# COTS.net
KiCad netlist of a schematic drawn in EAGLE
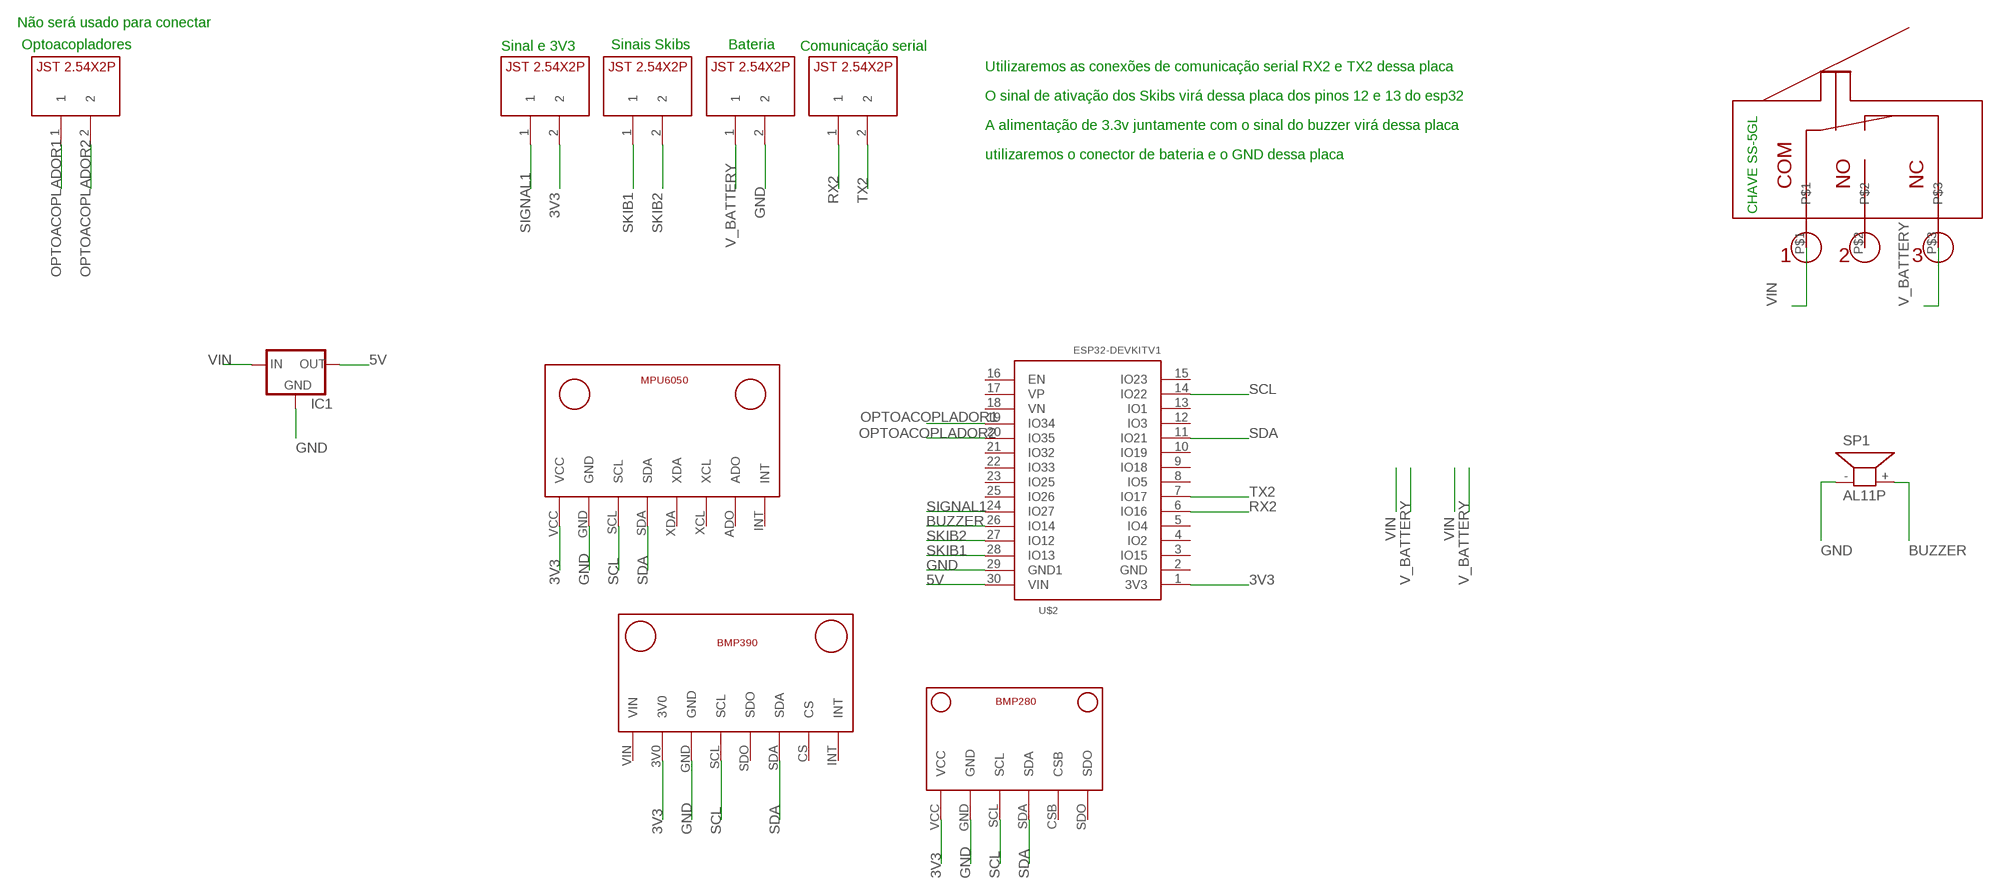
[diagram p0: schematic, sheet 1]

(export (version "E")
  (design (tool "Eeschema 10.0.6"))
  (components
    (comp (ref "IC1")
      (value "78XXL")
      (footprint "eagle-import:78XXL")
      (libsource (lib "eagle-import") (part "78XXL"))
    )
    (comp (ref "SP1")
      (value "AL11P")
      (footprint "eagle-import:AL11P")
      (libsource (lib "eagle-import") (part "AL11P"))
    )
    (comp (ref "U$1")
      (value "MPU6050V1")
      (footprint "eagle-import:MPU6050_FOOTPRINT")
      (libsource (lib "eagle-import") (part "MPU6050V1"))
    )
    (comp (ref "U$2")
      (value "ESP32DEVKITV1")
      (footprint "eagle-import:ESP32-DEVKITV1")
      (libsource (lib "eagle-import") (part "ESP32DEVKITV1"))
    )
    (comp (ref "U$3")
      (value "BMP390V1")
      (footprint "eagle-import:BMP390_FOOTPRINT")
      (libsource (lib "eagle-import") (part "BMP390V1"))
    )
    (comp (ref "U$4")
      (value "JST2.54X2P")
      (footprint "eagle-import:JST2.54X2P_FOOTPRINT")
      (libsource (lib "eagle-import") (part "JST2.54X2P"))
    )
    (comp (ref "U$5")
      (value "JST2.54X2P")
      (footprint "eagle-import:JST2.54X2P_FOOTPRINT")
      (libsource (lib "eagle-import") (part "JST2.54X2P"))
    )
    (comp (ref "U$6")
      (value "JST2.54X2P")
      (footprint "eagle-import:JST2.54X2P_FOOTPRINT")
      (libsource (lib "eagle-import") (part "JST2.54X2P"))
    )
    (comp (ref "U$7")
      (value "JST2.54X2P")
      (footprint "eagle-import:JST2.54X2P_FOOTPRINT")
      (libsource (lib "eagle-import") (part "JST2.54X2P"))
    )
    (comp (ref "U$8")
      (value "CHAVE_SS-5GL")
      (footprint "eagle-import:CHAVESS-5GL")
      (libsource (lib "eagle-import") (part "CHAVE_SS-5GL"))
    )
    (comp (ref "U$9")
      (value "JST2.54X2P")
      (footprint "eagle-import:JST2.54X2P_FOOTPRINT")
      (libsource (lib "eagle-import") (part "JST2.54X2P"))
    )
    (comp (ref "U$10")
      (value "BMP280V1")
      (footprint "eagle-import:BMP280_FOOTPRINT")
      (libsource (lib "eagle-import") (part "BMP280V1"))
    )
  )
  (nets
    (net (code "1") (name "/3V3") (class "Default")
      (node (ref "U$1") (pin "VCC") (pinfunction "VCC_VCC") (pintype "bidirectional"))
      (node (ref "U$10") (pin "VCC") (pinfunction "VCC_VCC") (pintype "bidirectional"))
      (node (ref "U$2") (pin "1") (pinfunction "3V3_1") (pintype "bidirectional"))
      (node (ref "U$3") (pin "3V0") (pinfunction "3V0_3V0") (pintype "bidirectional"))
      (node (ref "U$5") (pin "2") (pinfunction "2_2") (pintype "bidirectional"))
    )
    (net (code "2") (name "/5V") (class "Default")
      (node (ref "IC1") (pin "OUT") (pinfunction "OUT_OUT") (pintype "passive"))
      (node (ref "U$2") (pin "30") (pinfunction "VIN_30") (pintype "bidirectional"))
    )
    (net (code "3") (name "/BUZZER") (class "Default")
      (node (ref "SP1") (pin "+") (pinfunction "2_+") (pintype "passive"))
      (node (ref "U$2") (pin "26") (pinfunction "IO14_26") (pintype "bidirectional"))
    )
    (net (code "4") (name "/GND") (class "Default")
      (node (ref "IC1") (pin "GND") (pinfunction "GND_GND") (pintype "input"))
      (node (ref "SP1") (pin "-") (pinfunction "1_-") (pintype "passive"))
      (node (ref "U$1") (pin "GND") (pinfunction "GND_GND") (pintype "bidirectional"))
      (node (ref "U$10") (pin "GND") (pinfunction "GND_GND") (pintype "bidirectional"))
      (node (ref "U$2") (pin "29") (pinfunction "GND1_29") (pintype "bidirectional"))
      (node (ref "U$3") (pin "GND") (pinfunction "GND_GND") (pintype "bidirectional"))
      (node (ref "U$6") (pin "2") (pinfunction "2_2") (pintype "bidirectional"))
    )
    (net (code "5") (name "/OPTOACOPLADOR1") (class "Default")
      (node (ref "U$2") (pin "19") (pinfunction "IO34_19") (pintype "bidirectional"))
      (node (ref "U$9") (pin "1") (pinfunction "1_1") (pintype "bidirectional"))
    )
    (net (code "6") (name "/OPTOACOPLADOR2") (class "Default")
      (node (ref "U$2") (pin "20") (pinfunction "IO35_20") (pintype "bidirectional"))
      (node (ref "U$9") (pin "2") (pinfunction "2_2") (pintype "bidirectional"))
    )
    (net (code "7") (name "/RX2") (class "Default")
      (node (ref "U$2") (pin "6") (pinfunction "IO16_6") (pintype "bidirectional"))
      (node (ref "U$7") (pin "1") (pinfunction "1_1") (pintype "bidirectional"))
    )
    (net (code "8") (name "/SCL") (class "Default")
      (node (ref "U$1") (pin "SCL") (pinfunction "SCL_SCL") (pintype "bidirectional"))
      (node (ref "U$10") (pin "SCL") (pinfunction "SCL_SCL") (pintype "bidirectional"))
      (node (ref "U$2") (pin "14") (pinfunction "IO22_14") (pintype "bidirectional"))
      (node (ref "U$3") (pin "SCL") (pinfunction "SCL_SCL") (pintype "bidirectional"))
    )
    (net (code "9") (name "/SDA") (class "Default")
      (node (ref "U$1") (pin "SDA") (pinfunction "SDA_SDA") (pintype "bidirectional"))
      (node (ref "U$10") (pin "SDA") (pinfunction "SDA_SDA") (pintype "bidirectional"))
      (node (ref "U$2") (pin "11") (pinfunction "IO21_11") (pintype "bidirectional"))
      (node (ref "U$3") (pin "SDA") (pinfunction "SDA_SDA") (pintype "bidirectional"))
    )
    (net (code "10") (name "/SIGNAL1") (class "Default")
      (node (ref "U$2") (pin "24") (pinfunction "IO27_24") (pintype "bidirectional"))
      (node (ref "U$5") (pin "1") (pinfunction "1_1") (pintype "bidirectional"))
    )
    (net (code "11") (name "/SKIB1") (class "Default")
      (node (ref "U$2") (pin "28") (pinfunction "IO13_28") (pintype "bidirectional"))
      (node (ref "U$4") (pin "1") (pinfunction "1_1") (pintype "bidirectional"))
    )
    (net (code "12") (name "/SKIB2") (class "Default")
      (node (ref "U$2") (pin "27") (pinfunction "IO12_27") (pintype "bidirectional"))
      (node (ref "U$4") (pin "2") (pinfunction "2_2") (pintype "bidirectional"))
    )
    (net (code "13") (name "/TX2") (class "Default")
      (node (ref "U$2") (pin "7") (pinfunction "IO17_7") (pintype "bidirectional"))
      (node (ref "U$7") (pin "2") (pinfunction "2_2") (pintype "bidirectional"))
    )
    (net (code "14") (name "/VIN") (class "Default")
      (node (ref "IC1") (pin "IN") (pinfunction "IN_IN") (pintype "input"))
      (node (ref "U$8") (pin "P$1") (pinfunction "P$1_P$1") (pintype "bidirectional"))
    )
    (net (code "15") (name "/V_BATTERY") (class "Default")
      (node (ref "U$6") (pin "1") (pinfunction "1_1") (pintype "bidirectional"))
      (node (ref "U$8") (pin "P$3") (pinfunction "P$3_P$3") (pintype "bidirectional"))
    )
    (net (code "16") (name "unconnected-(U$1-PadADO)") (class "Default")
      (node (ref "U$1") (pin "ADO") (pinfunction "ADO_ADO") (pintype "bidirectional"))
    )
    (net (code "17") (name "unconnected-(U$1-PadINT)") (class "Default")
      (node (ref "U$1") (pin "INT") (pinfunction "INT_INT") (pintype "bidirectional"))
    )
    (net (code "18") (name "unconnected-(U$1-PadXCL)") (class "Default")
      (node (ref "U$1") (pin "XCL") (pinfunction "XCL_XCL") (pintype "bidirectional"))
    )
    (net (code "19") (name "unconnected-(U$1-PadXDA)") (class "Default")
      (node (ref "U$1") (pin "XDA") (pinfunction "XDA_XDA") (pintype "bidirectional"))
    )
    (net (code "20") (name "unconnected-(U$2-EN-Pad16)") (class "Default")
      (node (ref "U$2") (pin "16") (pinfunction "EN_16") (pintype "bidirectional"))
    )
    (net (code "21") (name "unconnected-(U$2-GND-Pad2)") (class "Default")
      (node (ref "U$2") (pin "2") (pinfunction "GND_2") (pintype "bidirectional"))
    )
    (net (code "22") (name "unconnected-(U$2-IO1-Pad13)") (class "Default")
      (node (ref "U$2") (pin "13") (pinfunction "IO1_13") (pintype "bidirectional"))
    )
    (net (code "23") (name "unconnected-(U$2-IO2-Pad4)") (class "Default")
      (node (ref "U$2") (pin "4") (pinfunction "IO2_4") (pintype "bidirectional"))
    )
    (net (code "24") (name "unconnected-(U$2-IO3-Pad12)") (class "Default")
      (node (ref "U$2") (pin "12") (pinfunction "IO3_12") (pintype "bidirectional"))
    )
    (net (code "25") (name "unconnected-(U$2-IO4-Pad5)") (class "Default")
      (node (ref "U$2") (pin "5") (pinfunction "IO4_5") (pintype "bidirectional"))
    )
    (net (code "26") (name "unconnected-(U$2-IO5-Pad8)") (class "Default")
      (node (ref "U$2") (pin "8") (pinfunction "IO5_8") (pintype "bidirectional"))
    )
    (net (code "27") (name "unconnected-(U$2-IO15-Pad3)") (class "Default")
      (node (ref "U$2") (pin "3") (pinfunction "IO15_3") (pintype "bidirectional"))
    )
    (net (code "28") (name "unconnected-(U$2-IO18-Pad9)") (class "Default")
      (node (ref "U$2") (pin "9") (pinfunction "IO18_9") (pintype "bidirectional"))
    )
    (net (code "29") (name "unconnected-(U$2-IO19-Pad10)") (class "Default")
      (node (ref "U$2") (pin "10") (pinfunction "IO19_10") (pintype "bidirectional"))
    )
    (net (code "30") (name "unconnected-(U$2-IO23-Pad15)") (class "Default")
      (node (ref "U$2") (pin "15") (pinfunction "IO23_15") (pintype "bidirectional"))
    )
    (net (code "31") (name "unconnected-(U$2-IO25-Pad23)") (class "Default")
      (node (ref "U$2") (pin "23") (pinfunction "IO25_23") (pintype "bidirectional"))
    )
    (net (code "32") (name "unconnected-(U$2-IO26-Pad25)") (class "Default")
      (node (ref "U$2") (pin "25") (pinfunction "IO26_25") (pintype "bidirectional"))
    )
    (net (code "33") (name "unconnected-(U$2-IO32-Pad21)") (class "Default")
      (node (ref "U$2") (pin "21") (pinfunction "IO32_21") (pintype "bidirectional"))
    )
    (net (code "34") (name "unconnected-(U$2-IO33-Pad22)") (class "Default")
      (node (ref "U$2") (pin "22") (pinfunction "IO33_22") (pintype "bidirectional"))
    )
    (net (code "35") (name "unconnected-(U$2-VN-Pad18)") (class "Default")
      (node (ref "U$2") (pin "18") (pinfunction "VN_18") (pintype "bidirectional"))
    )
    (net (code "36") (name "unconnected-(U$2-VP-Pad17)") (class "Default")
      (node (ref "U$2") (pin "17") (pinfunction "VP_17") (pintype "bidirectional"))
    )
    (net (code "37") (name "unconnected-(U$3-PadCS)") (class "Default")
      (node (ref "U$3") (pin "CS") (pinfunction "CS_CS") (pintype "bidirectional"))
    )
    (net (code "38") (name "unconnected-(U$3-PadINT)") (class "Default")
      (node (ref "U$3") (pin "INT") (pinfunction "INT_INT") (pintype "bidirectional"))
    )
    (net (code "39") (name "unconnected-(U$3-PadSDO)") (class "Default")
      (node (ref "U$3") (pin "SDO") (pinfunction "SDO_SDO") (pintype "bidirectional"))
    )
    (net (code "40") (name "unconnected-(U$3-PadVIN)") (class "Default")
      (node (ref "U$3") (pin "VIN") (pinfunction "VIN_VIN") (pintype "bidirectional"))
    )
    (net (code "41") (name "unconnected-(U$8-PadP$2)") (class "Default")
      (node (ref "U$8") (pin "P$2") (pinfunction "P$2_P$2") (pintype "bidirectional"))
    )
    (net (code "42") (name "unconnected-(U$10-PadCSB)") (class "Default")
      (node (ref "U$10") (pin "CSB") (pinfunction "CSB_CSB") (pintype "bidirectional"))
    )
    (net (code "43") (name "unconnected-(U$10-PadSDO)") (class "Default")
      (node (ref "U$10") (pin "SDO") (pinfunction "SDO_SDO") (pintype "bidirectional"))
    )
  )
)
